# PCICARD_-PCI-PADS-Ax-Bx.net
KiCad netlist of a schematic drawn in Altium Designer
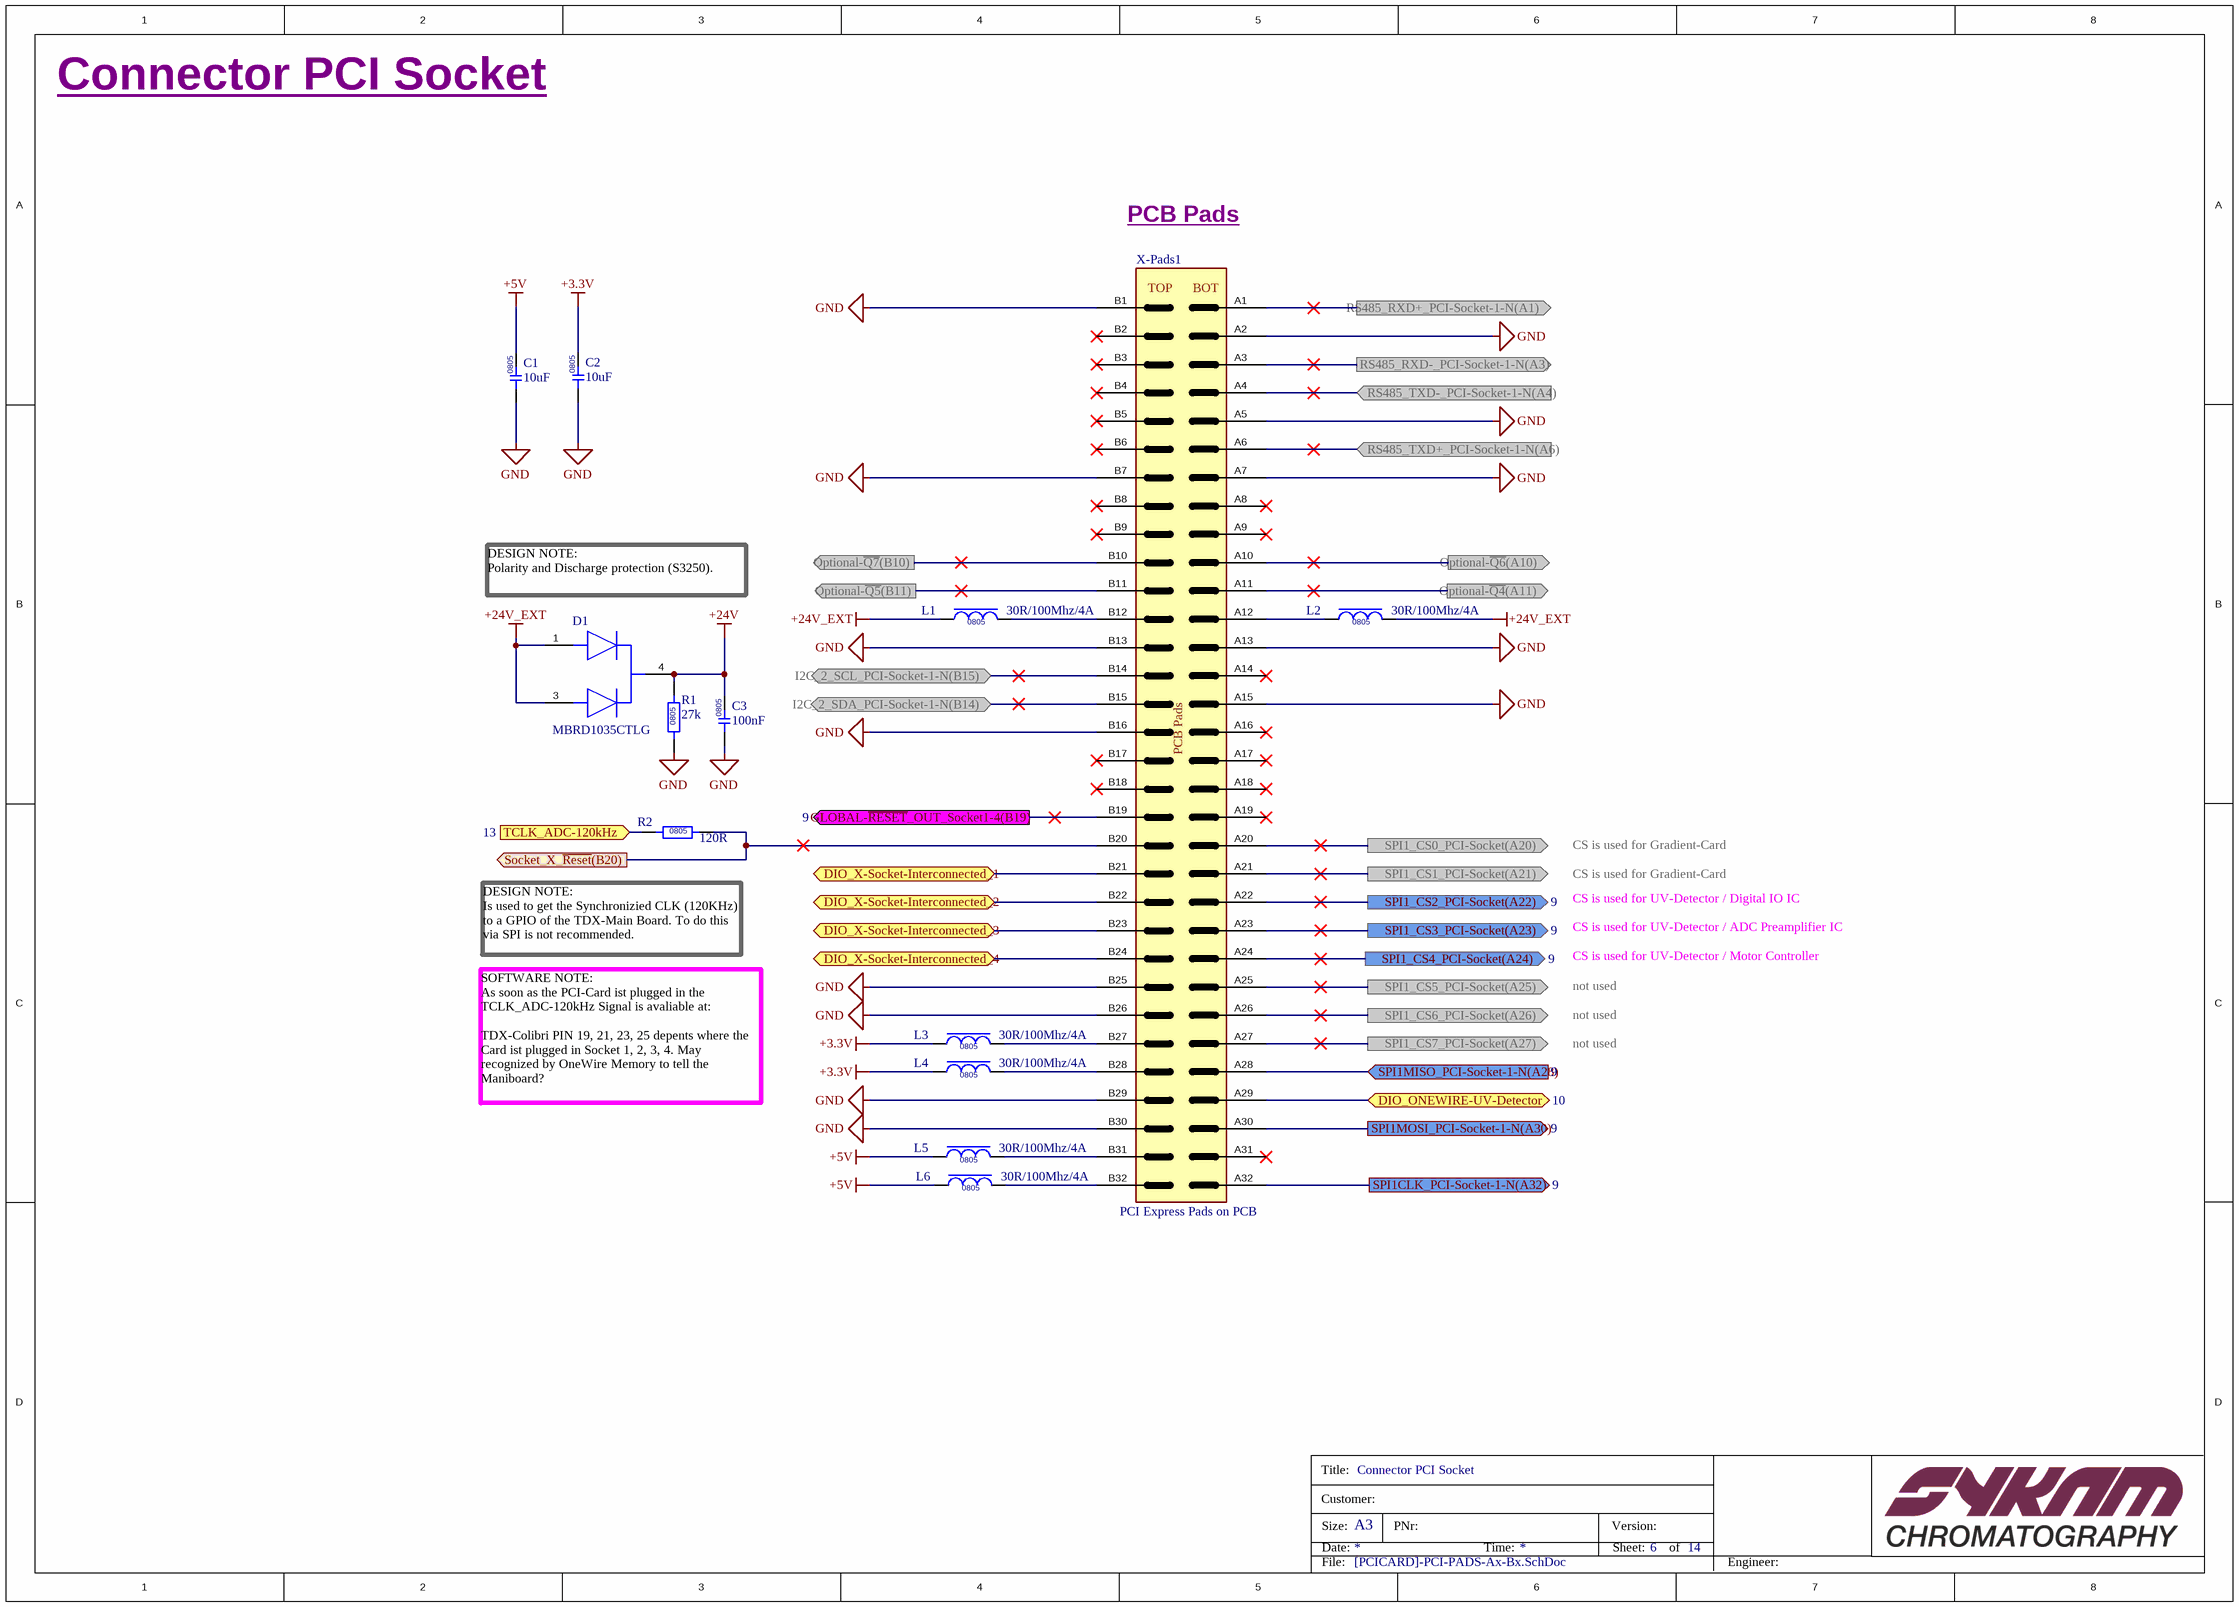
[diagram p0: [PCICARD]-PCI-PADS-Ax-Bx.SchDoc]

(export (version "E")
  (design (tool "Eeschema 10.0.6"))
  (components
    (comp (ref "C1")
      (value "10uF")
      (footprint "C0805")
      (description "0805 10 uF 50 V ±20% Tolerance X5R Multilayer Ceramic Capacitor")
      (fields
        (field (name "MANUFACTURER") "Murata")
        (field (name "MANUFACTURER PART NUMBER") "GRM21BR6YA106ME43L")
      )
      (libsource (lib "ToradexMainBoard-V0I1") (part "C_10uF_GRM21BR6YA106ME43L"))
    )
    (comp (ref "C2")
      (value "10uF")
      (footprint "C0805")
      (description "0805 10 uF 50 V ±20% Tolerance X5R Multilayer Ceramic Capacitor")
      (fields
        (field (name "MANUFACTURER") "Murata")
        (field (name "MANUFACTURER PART NUMBER") "GRM21BR6YA106ME43L")
      )
      (libsource (lib "ToradexMainBoard-V0I1") (part "C_10uF_GRM21BR6YA106ME43L"))
    )
    (comp (ref "C3")
      (value "100nF")
      (footprint "C0805")
      (description "CAP CER 0.1UF 50V X7R 0805")
      (fields
        (field (name "MANUFACTURER PART NUMBER") "CC0805KRX7R9BB104")
        (field (name "TOLERANCE") "10%")
        (field (name "PCBCHECKED") "initials after Checked")
        (field (name "SCHCHECKED") "Initials after checked")
      )
      (libsource (lib "ToradexMainBoard-V0I1") (part "C_100nF_CC0805KRX7R9BB104"))
    )
    (comp (ref "D1")
      (value "MBRD1035CTLG")
      (footprint "MBRD1035CTLG-DPak")
      (description "ON Semi MBRD1035CTLG; Dual SMT Schottky Diode; Common Cathode; 35V 10A; 3-Pin D-PAK")
      (fields (field (name "MANUFACTURER") "ON Semiconductor"))
      (libsource (lib "ToradexMainBoard-V0I1") (part "D_MBRD1035CTLG"))
    )
    (comp (ref "L1")
      (value "30R/100Mhz/4A")
      (footprint "L0805")
      (description "Ferrite Beads Multi-Layer 30Ohm 100MHz 4A 14mOhm DCR 0805 T/R")
      (fields
        (field (name "MANUFACTURER PART NUMBER") "BLM21PG300SN1D")
        (field (name "TOLERANCE") "25%")
        (field (name "PCBCHECKED") "initials after Checked")
        (field (name "SCHCHECKED") "Initials after checked")
      )
      (libsource (lib "ToradexMainBoard-V0I1") (part "L_BLM21PG300SN1D_1"))
    )
    (comp (ref "L2")
      (value "30R/100Mhz/4A")
      (footprint "L0805")
      (description "Ferrite Beads Multi-Layer 30Ohm 100MHz 4A 14mOhm DCR 0805 T/R")
      (fields
        (field (name "MANUFACTURER PART NUMBER") "BLM21PG300SN1D")
        (field (name "TOLERANCE") "25%")
        (field (name "PCBCHECKED") "initials after Checked")
        (field (name "SCHCHECKED") "Initials after checked")
      )
      (libsource (lib "ToradexMainBoard-V0I1") (part "L_BLM21PG300SN1D_1"))
    )
    (comp (ref "L3")
      (value "30R/100Mhz/4A")
      (footprint "L0805")
      (description "Ferrite Beads Multi-Layer 30Ohm 100MHz 4A 14mOhm DCR 0805 T/R")
      (fields
        (field (name "MANUFACTURER PART NUMBER") "BLM21PG300SN1D")
        (field (name "TOLERANCE") "25%")
        (field (name "PCBCHECKED") "initials after Checked")
        (field (name "SCHCHECKED") "Initials after checked")
      )
      (libsource (lib "ToradexMainBoard-V0I1") (part "L_BLM21PG300SN1D_1"))
    )
    (comp (ref "L4")
      (value "30R/100Mhz/4A")
      (footprint "L0805")
      (description "Ferrite Beads Multi-Layer 30Ohm 100MHz 4A 14mOhm DCR 0805 T/R")
      (fields
        (field (name "MANUFACTURER PART NUMBER") "BLM21PG300SN1D")
        (field (name "TOLERANCE") "25%")
        (field (name "PCBCHECKED") "initials after Checked")
        (field (name "SCHCHECKED") "Initials after checked")
      )
      (libsource (lib "ToradexMainBoard-V0I1") (part "L_BLM21PG300SN1D_1"))
    )
    (comp (ref "L5")
      (value "30R/100Mhz/4A")
      (footprint "L0805")
      (description "Ferrite Beads Multi-Layer 30Ohm 100MHz 4A 14mOhm DCR 0805 T/R")
      (fields
        (field (name "MANUFACTURER PART NUMBER") "BLM21PG300SN1D")
        (field (name "TOLERANCE") "25%")
        (field (name "PCBCHECKED") "initials after Checked")
        (field (name "SCHCHECKED") "Initials after checked")
      )
      (libsource (lib "ToradexMainBoard-V0I1") (part "L_BLM21PG300SN1D_1"))
    )
    (comp (ref "L6")
      (value "30R/100Mhz/4A")
      (footprint "L0805")
      (description "Ferrite Beads Multi-Layer 30Ohm 100MHz 4A 14mOhm DCR 0805 T/R")
      (fields
        (field (name "MANUFACTURER PART NUMBER") "BLM21PG300SN1D")
        (field (name "TOLERANCE") "25%")
        (field (name "PCBCHECKED") "initials after Checked")
        (field (name "SCHCHECKED") "Initials after checked")
      )
      (libsource (lib "ToradexMainBoard-V0I1") (part "L_BLM21PG300SN1D_1"))
    )
    (comp (ref "R1")
      (value "27k")
      (footprint "R0805")
      (description "Surface Mount Thick Film Resistor, RC Series, 27 kohm, 125 mW, - 1%, 150 V, 0805 [2012 Metric]")
      (fields
        (field (name "MANUFACTURER") "Yageo")
        (field (name "MANUFACTURER PART NUMBER") "RC0805FR-0727KL")
      )
      (libsource (lib "ToradexMainBoard-V0I1") (part "R_27k_RC0805FR-0727KL"))
    )
    (comp (ref "R2")
      (value "120R")
      (footprint "R0805")
      (description "RES SMD 120 OHM 1% 1/8W 0805")
      (fields
        (field (name "MANUFACTURER PART NUMBER") "RC0805FR-07120RL")
        (field (name "TOLERANCE") "1%")
        (field (name "PCBCHECKED") "initials after Checked")
        (field (name "SCHCHECKED") "Initials after checked")
      )
      (libsource (lib "ToradexMainBoard-V0I1") (part "R_120R_RC0805FR-07120RL"))
    )
    (comp (ref "X-Pads1")
      (value "PCI Express Pads on PCB")
      (footprint "PCI_Express_64_Pads")
      (libsource (lib "Sykam-Mech1") (part "PCI_Connector_64PINs_AB"))
    )
  )
  (nets
    (net (code "1") (name "+3.3V") (class "Default")
      (node (ref "C2") (pin "2") (pinfunction "2_2") (pintype "passive"))
      (node (ref "L3") (pin "1") (pinfunction "1_1") (pintype "passive"))
      (node (ref "L4") (pin "1") (pinfunction "1_1") (pintype "passive"))
    )
    (net (code "2") (name "+5V") (class "Default")
      (node (ref "C1") (pin "2") (pinfunction "2_2") (pintype "passive"))
      (node (ref "L5") (pin "1") (pinfunction "1_1") (pintype "passive"))
      (node (ref "L6") (pin "1") (pinfunction "1_1") (pintype "passive"))
    )
    (net (code "3") (name "+24V") (class "Default")
      (node (ref "C3") (pin "2") (pinfunction "2_2") (pintype "passive"))
      (node (ref "D1") (pin "4") (pinfunction "C_4") (pintype "passive"))
      (node (ref "R1") (pin "2") (pinfunction "2_2") (pintype "passive"))
    )
    (net (code "4") (name "+24V_EXT") (class "Default")
      (node (ref "D1") (pin "1") (pinfunction "A_1") (pintype "passive"))
      (node (ref "D1") (pin "3") (pinfunction "A_3") (pintype "passive"))
      (node (ref "L1") (pin "1") (pinfunction "1_1") (pintype "passive"))
      (node (ref "L2") (pin "2") (pinfunction "2_2") (pintype "passive"))
    )
    (net (code "5") (name "/DIO_ONEWIRE-UV-Detector") (class "Default")
      (node (ref "X-Pads1") (pin "A29") (pinfunction "A_A29") (pintype "passive"))
    )
    (net (code "6") (name "/DIO_X-Socket-Interconnected_1") (class "Default")
      (node (ref "X-Pads1") (pin "B21") (pinfunction "B_B21") (pintype "passive"))
    )
    (net (code "7") (name "/DIO_X-Socket-Interconnected_2") (class "Default")
      (node (ref "X-Pads1") (pin "B22") (pinfunction "B_B22") (pintype "passive"))
    )
    (net (code "8") (name "/DIO_X-Socket-Interconnected_3") (class "Default")
      (node (ref "X-Pads1") (pin "B23") (pinfunction "B_B23") (pintype "passive"))
    )
    (net (code "9") (name "/DIO_X-Socket-Interconnected_4") (class "Default")
      (node (ref "X-Pads1") (pin "B24") (pinfunction "B_B24") (pintype "passive"))
    )
    (net (code "10") (name "/GLOBAL-~{RESET}_OUT_Socket1-4(B19)") (class "Default")
      (node (ref "X-Pads1") (pin "B19") (pinfunction "B_B19") (pintype "passive"))
    )
    (net (code "11") (name "/I2C_2_SCL_PCI-Socket-1-N(B15)") (class "Default")
      (node (ref "X-Pads1") (pin "B14") (pinfunction "B14_B14") (pintype "passive"))
    )
    (net (code "12") (name "/I2C_2_SDA_PCI-Socket-1-N(B14)") (class "Default")
      (node (ref "X-Pads1") (pin "B15") (pinfunction "B15_B15") (pintype "passive"))
    )
    (net (code "13") (name "/Optional-~{Q4}(A11)") (class "Default")
      (node (ref "X-Pads1") (pin "A11") (pinfunction "A11_A11") (pintype "passive"))
    )
    (net (code "14") (name "/Optional-~{Q5}(B11)") (class "Default")
      (node (ref "X-Pads1") (pin "B11") (pinfunction "B11_B11") (pintype "passive"))
    )
    (net (code "15") (name "/Optional-~{Q6}(A10)") (class "Default")
      (node (ref "X-Pads1") (pin "A10") (pinfunction "A10_A10") (pintype "passive"))
    )
    (net (code "16") (name "/Optional-~{Q7}(B10)") (class "Default")
      (node (ref "X-Pads1") (pin "B10") (pinfunction "B10_B10") (pintype "passive"))
    )
    (net (code "17") (name "/RS485_RXD+_PCI-Socket-1-N(A1)") (class "Default")
      (node (ref "X-Pads1") (pin "A1") (pinfunction "A1_A1") (pintype "passive"))
    )
    (net (code "18") (name "/RS485_RXD-_PCI-Socket-1-N(A3)") (class "Default")
      (node (ref "X-Pads1") (pin "A3") (pinfunction "A3_A3") (pintype "passive"))
    )
    (net (code "19") (name "/RS485_TXD+_PCI-Socket-1-N(A6)") (class "Default")
      (node (ref "X-Pads1") (pin "A6") (pinfunction "A6_A6") (pintype "passive"))
    )
    (net (code "20") (name "/RS485_TXD-_PCI-Socket-1-N(A4)") (class "Default")
      (node (ref "X-Pads1") (pin "A4") (pinfunction "A4_A4") (pintype "passive"))
    )
    (net (code "21") (name "/SPI1CLK_PCI-Socket-1-N(A32)") (class "Default")
      (node (ref "X-Pads1") (pin "A32") (pinfunction "A_A32") (pintype "passive"))
    )
    (net (code "22") (name "/SPI1MISO_PCI-Socket-1-N(A28)") (class "Default")
      (node (ref "X-Pads1") (pin "A28") (pinfunction "A_A28") (pintype "passive"))
    )
    (net (code "23") (name "/SPI1MOSI_PCI-Socket-1-N(A30)") (class "Default")
      (node (ref "X-Pads1") (pin "A30") (pinfunction "A_A30") (pintype "passive"))
    )
    (net (code "24") (name "/SPI1_CS0_PCI-Socket(A20)") (class "Default")
      (node (ref "X-Pads1") (pin "A20") (pinfunction "A_A20") (pintype "passive"))
    )
    (net (code "25") (name "/SPI1_CS1_PCI-Socket(A21)") (class "Default")
      (node (ref "X-Pads1") (pin "A21") (pinfunction "A_A21") (pintype "passive"))
    )
    (net (code "26") (name "/SPI1_CS2_PCI-Socket(A22)") (class "Default")
      (node (ref "X-Pads1") (pin "A22") (pinfunction "A_A22") (pintype "passive"))
    )
    (net (code "27") (name "/SPI1_CS3_PCI-Socket(A23)") (class "Default")
      (node (ref "X-Pads1") (pin "A23") (pinfunction "A_A23") (pintype "passive"))
    )
    (net (code "28") (name "/SPI1_CS4_PCI-Socket(A24)") (class "Default")
      (node (ref "X-Pads1") (pin "A24") (pinfunction "A_A24") (pintype "passive"))
    )
    (net (code "29") (name "/SPI1_CS5_PCI-Socket(A25)") (class "Default")
      (node (ref "X-Pads1") (pin "A25") (pinfunction "A_A25") (pintype "passive"))
    )
    (net (code "30") (name "/SPI1_CS6_PCI-Socket(A26)") (class "Default")
      (node (ref "X-Pads1") (pin "A26") (pinfunction "A_A26") (pintype "passive"))
    )
    (net (code "31") (name "/SPI1_CS7_PCI-Socket(A27)") (class "Default")
      (node (ref "X-Pads1") (pin "A27") (pinfunction "A_A27") (pintype "passive"))
    )
    (net (code "32") (name "/Socket_X_~{Reset}(B20)") (class "Default")
      (node (ref "R2") (pin "2") (pinfunction "2_2") (pintype "passive"))
      (node (ref "X-Pads1") (pin "B20") (pinfunction "B_B20") (pintype "passive"))
    )
    (net (code "33") (name "/TCLK_ADC-120kHz") (class "Default")
      (node (ref "R2") (pin "1") (pinfunction "1_1") (pintype "passive"))
    )
    (net (code "34") (name "GND") (class "Default")
      (node (ref "C1") (pin "1") (pinfunction "1_1") (pintype "passive"))
      (node (ref "C2") (pin "1") (pinfunction "1_1") (pintype "passive"))
      (node (ref "C3") (pin "1") (pinfunction "1_1") (pintype "passive"))
      (node (ref "R1") (pin "1") (pinfunction "1_1") (pintype "passive"))
      (node (ref "X-Pads1") (pin "A13") (pinfunction "A13_A13") (pintype "passive"))
      (node (ref "X-Pads1") (pin "A15") (pinfunction "A15_A15") (pintype "passive"))
      (node (ref "X-Pads1") (pin "A2") (pinfunction "A2_A2") (pintype "passive"))
      (node (ref "X-Pads1") (pin "A5") (pinfunction "A5_A5") (pintype "passive"))
      (node (ref "X-Pads1") (pin "A7") (pinfunction "A7_A7") (pintype "passive"))
      (node (ref "X-Pads1") (pin "B1") (pinfunction "B1_B1") (pintype "passive"))
      (node (ref "X-Pads1") (pin "B13") (pinfunction "B13_B13") (pintype "passive"))
      (node (ref "X-Pads1") (pin "B16") (pinfunction "B16_B16") (pintype "passive"))
      (node (ref "X-Pads1") (pin "B25") (pinfunction "B_B25") (pintype "passive"))
      (node (ref "X-Pads1") (pin "B26") (pinfunction "B_B26") (pintype "passive"))
      (node (ref "X-Pads1") (pin "B29") (pinfunction "B_B29") (pintype "passive"))
      (node (ref "X-Pads1") (pin "B30") (pinfunction "B_B30") (pintype "passive"))
      (node (ref "X-Pads1") (pin "B7") (pinfunction "B7_B7") (pintype "passive"))
    )
    (net (code "35") (name "Net-(L1-Pad2)") (class "Default")
      (node (ref "L1") (pin "2") (pinfunction "2_2") (pintype "passive"))
      (node (ref "X-Pads1") (pin "B12") (pinfunction "B12_B12") (pintype "passive"))
    )
    (net (code "36") (name "Net-(L2-Pad1)") (class "Default")
      (node (ref "L2") (pin "1") (pinfunction "1_1") (pintype "passive"))
      (node (ref "X-Pads1") (pin "A12") (pinfunction "A12_A12") (pintype "passive"))
    )
    (net (code "37") (name "Net-(L3-Pad2)") (class "Default")
      (node (ref "L3") (pin "2") (pinfunction "2_2") (pintype "passive"))
      (node (ref "X-Pads1") (pin "B27") (pinfunction "B_B27") (pintype "passive"))
    )
    (net (code "38") (name "Net-(L4-Pad2)") (class "Default")
      (node (ref "L4") (pin "2") (pinfunction "2_2") (pintype "passive"))
      (node (ref "X-Pads1") (pin "B28") (pinfunction "B_B28") (pintype "passive"))
    )
    (net (code "39") (name "Net-(L5-Pad2)") (class "Default")
      (node (ref "L5") (pin "2") (pinfunction "2_2") (pintype "passive"))
      (node (ref "X-Pads1") (pin "B31") (pinfunction "B_B31") (pintype "passive"))
    )
    (net (code "40") (name "Net-(L6-Pad2)") (class "Default")
      (node (ref "L6") (pin "2") (pinfunction "2_2") (pintype "passive"))
      (node (ref "X-Pads1") (pin "B32") (pinfunction "B_B32") (pintype "passive"))
    )
    (net (code "41") (name "unconnected-(X-Pads1-A-PadA19)") (class "Default")
      (node (ref "X-Pads1") (pin "A19") (pinfunction "A_A19") (pintype "passive+no_connect"))
    )
    (net (code "42") (name "unconnected-(X-Pads1-A-PadA31)") (class "Default")
      (node (ref "X-Pads1") (pin "A31") (pinfunction "A_A31") (pintype "passive+no_connect"))
    )
    (net (code "43") (name "unconnected-(X-Pads1-PadA8)") (class "Default")
      (node (ref "X-Pads1") (pin "A8") (pinfunction "A8_A8") (pintype "passive+no_connect"))
    )
    (net (code "44") (name "unconnected-(X-Pads1-PadA9)") (class "Default")
      (node (ref "X-Pads1") (pin "A9") (pinfunction "A9_A9") (pintype "passive+no_connect"))
    )
    (net (code "45") (name "unconnected-(X-Pads1-PadA14)") (class "Default")
      (node (ref "X-Pads1") (pin "A14") (pinfunction "A14_A14") (pintype "passive+no_connect"))
    )
    (net (code "46") (name "unconnected-(X-Pads1-PadA16)") (class "Default")
      (node (ref "X-Pads1") (pin "A16") (pinfunction "A16_A16") (pintype "passive+no_connect"))
    )
    (net (code "47") (name "unconnected-(X-Pads1-PadA17)") (class "Default")
      (node (ref "X-Pads1") (pin "A17") (pinfunction "A17_A17") (pintype "passive+no_connect"))
    )
    (net (code "48") (name "unconnected-(X-Pads1-PadA18)") (class "Default")
      (node (ref "X-Pads1") (pin "A18") (pinfunction "A18_A18") (pintype "passive+no_connect"))
    )
    (net (code "49") (name "unconnected-(X-Pads1-PadB2)") (class "Default")
      (node (ref "X-Pads1") (pin "B2") (pinfunction "B2_B2") (pintype "passive+no_connect"))
    )
    (net (code "50") (name "unconnected-(X-Pads1-PadB3)") (class "Default")
      (node (ref "X-Pads1") (pin "B3") (pinfunction "B3_B3") (pintype "passive+no_connect"))
    )
    (net (code "51") (name "unconnected-(X-Pads1-PadB4)") (class "Default")
      (node (ref "X-Pads1") (pin "B4") (pinfunction "B4_B4") (pintype "passive+no_connect"))
    )
    (net (code "52") (name "unconnected-(X-Pads1-PadB5)") (class "Default")
      (node (ref "X-Pads1") (pin "B5") (pinfunction "B5_B5") (pintype "passive+no_connect"))
    )
    (net (code "53") (name "unconnected-(X-Pads1-PadB6)") (class "Default")
      (node (ref "X-Pads1") (pin "B6") (pinfunction "B6_B6") (pintype "passive+no_connect"))
    )
    (net (code "54") (name "unconnected-(X-Pads1-PadB8)") (class "Default")
      (node (ref "X-Pads1") (pin "B8") (pinfunction "B8_B8") (pintype "passive+no_connect"))
    )
    (net (code "55") (name "unconnected-(X-Pads1-PadB9)") (class "Default")
      (node (ref "X-Pads1") (pin "B9") (pinfunction "B9_B9") (pintype "passive+no_connect"))
    )
    (net (code "56") (name "unconnected-(X-Pads1-PadB17)") (class "Default")
      (node (ref "X-Pads1") (pin "B17") (pinfunction "B17_B17") (pintype "passive+no_connect"))
    )
    (net (code "57") (name "unconnected-(X-Pads1-PadB18)") (class "Default")
      (node (ref "X-Pads1") (pin "B18") (pinfunction "B18_B18") (pintype "passive+no_connect"))
    )
  )
)
